# LogBoard.net
KiCad netlist of a schematic drawn in EAGLE
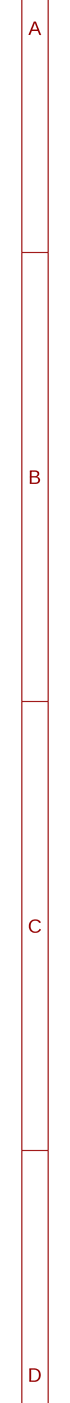
[diagram p0: schematic, sheet 1, part 1 of 2]
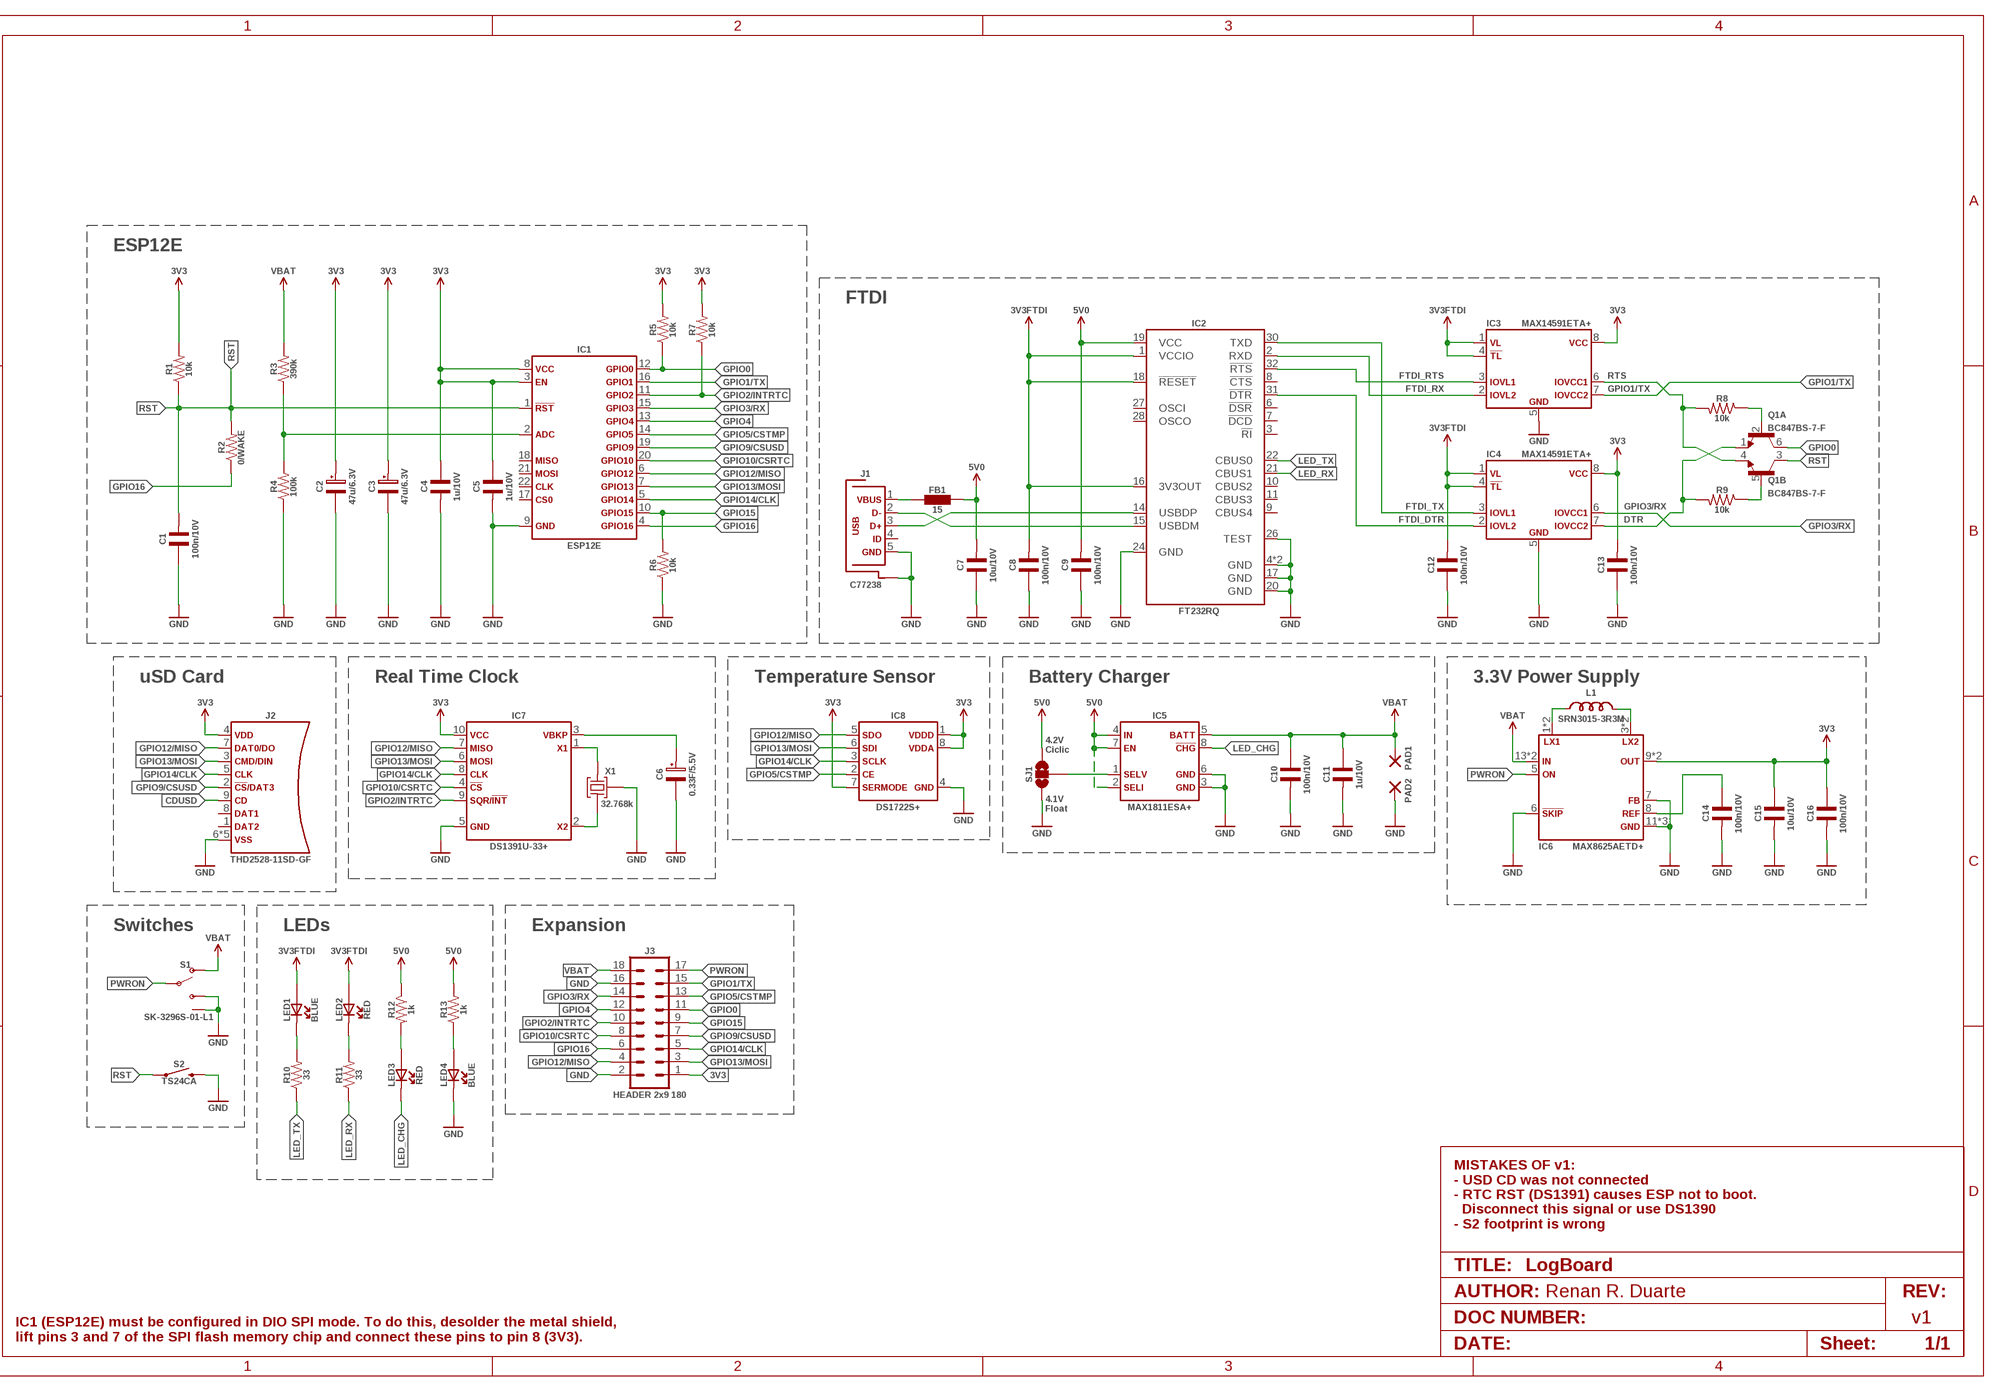
[diagram p1: schematic, sheet 1, part 2 of 2]

(export (version "E")
  (design (tool "Eeschema 10.0.6"))
  (components
    (comp (ref "C1")
      (value "100n/10V")
      (footprint "eagle-import:C-SMD-0603")
      (libsource (lib "eagle-import") (part "1-CAPACITORSMD-0603"))
    )
    (comp (ref "C2")
      (value "47u/6.3V")
      (footprint "eagle-import:C-SMD-CT3528")
      (libsource (lib "eagle-import") (part "1-CAPACITOR-POLCT3528"))
    )
    (comp (ref "C3")
      (value "47u/6.3V")
      (footprint "eagle-import:C-SMD-CT3528")
      (libsource (lib "eagle-import") (part "1-CAPACITOR-POLCT3528"))
    )
    (comp (ref "C4")
      (value "1u/10V")
      (footprint "eagle-import:C-SMD-0603")
      (libsource (lib "eagle-import") (part "1-CAPACITORSMD-0603"))
    )
    (comp (ref "C5")
      (value "1u/10V")
      (footprint "eagle-import:C-SMD-0603")
      (libsource (lib "eagle-import") (part "1-CAPACITORSMD-0603"))
    )
    (comp (ref "C6")
      (value "0.33F/5.5V")
      (footprint "eagle-import:C-PTH-5X11.5")
      (libsource (lib "eagle-import") (part "1-CAPACITOR-POL5X11.5"))
    )
    (comp (ref "C7")
      (value "10u/10V")
      (footprint "eagle-import:C-SMD-0603")
      (libsource (lib "eagle-import") (part "1-CAPACITORSMD-0603"))
    )
    (comp (ref "C8")
      (value "100n/10V")
      (footprint "eagle-import:C-SMD-0603")
      (libsource (lib "eagle-import") (part "1-CAPACITORSMD-0603"))
    )
    (comp (ref "C9")
      (value "100n/10V")
      (footprint "eagle-import:C-SMD-0603")
      (libsource (lib "eagle-import") (part "1-CAPACITORSMD-0603"))
    )
    (comp (ref "C10")
      (value "100n/10V")
      (footprint "eagle-import:C-SMD-0603")
      (libsource (lib "eagle-import") (part "1-CAPACITORSMD-0603"))
    )
    (comp (ref "C11")
      (value "1u/10V")
      (footprint "eagle-import:C-SMD-0603")
      (libsource (lib "eagle-import") (part "1-CAPACITORSMD-0603"))
    )
    (comp (ref "C12")
      (value "100n/10V")
      (footprint "eagle-import:C-SMD-0603")
      (libsource (lib "eagle-import") (part "1-CAPACITORSMD-0603"))
    )
    (comp (ref "C13")
      (value "100n/10V")
      (footprint "eagle-import:C-SMD-0603")
      (libsource (lib "eagle-import") (part "1-CAPACITORSMD-0603"))
    )
    (comp (ref "C14")
      (value "100n/10V")
      (footprint "eagle-import:C-SMD-0603")
      (libsource (lib "eagle-import") (part "1-CAPACITORSMD-0603"))
    )
    (comp (ref "C15")
      (value "10u/10V")
      (footprint "eagle-import:C-SMD-0603")
      (libsource (lib "eagle-import") (part "1-CAPACITORSMD-0603"))
    )
    (comp (ref "C16")
      (value "100n/10V")
      (footprint "eagle-import:C-SMD-0603")
      (libsource (lib "eagle-import") (part "1-CAPACITORSMD-0603"))
    )
    (comp (ref "FB1")
      (value "15")
      (footprint "eagle-import:R-SMD-0603")
      (libsource (lib "eagle-import") (part "FB-0603"))
    )
    (comp (ref "IC1")
      (value "ESP12E")
      (footprint "eagle-import:IC-ESP8266-12E")
      (libsource (lib "eagle-import") (part "IC-ESP8266-12E"))
    )
    (comp (ref "IC2")
      (value "FT232RQ")
      (footprint "eagle-import:IC-QFN32")
      (libsource (lib "eagle-import") (part "IC-FT232RQ"))
    )
    (comp (ref "IC3")
      (value "MAX14591ETA+")
      (footprint "eagle-import:IC-TDFN8")
      (libsource (lib "eagle-import") (part "IC-MAX14591"))
    )
    (comp (ref "IC4")
      (value "MAX14591ETA+")
      (footprint "eagle-import:IC-TDFN8")
      (libsource (lib "eagle-import") (part "IC-MAX14591"))
    )
    (comp (ref "IC5")
      (value "MAX1811ESA+")
      (footprint "eagle-import:IC-SO8")
      (libsource (lib "eagle-import") (part "IC-MAX1811"))
    )
    (comp (ref "IC6")
      (value "MAX8625AETD+")
      (footprint "eagle-import:IC-TDFN14")
      (libsource (lib "eagle-import") (part "IC-MAX8625"))
    )
    (comp (ref "IC7")
      (value "DS1391U-33+")
      (footprint "eagle-import:IC-USOP10")
      (libsource (lib "eagle-import") (part "IC-DS1394"))
    )
    (comp (ref "IC8")
      (value "DS1722S+")
      (footprint "eagle-import:IC-SO8")
      (libsource (lib "eagle-import") (part "IC-DS1722"))
    )
    (comp (ref "J1")
      (value "C77238")
      (footprint "eagle-import:CN-MICRO-USB")
      (libsource (lib "eagle-import") (part "CN-MICRO-USB"))
    )
    (comp (ref "J2")
      (value "THD2528-11SD-GF")
      (footprint "eagle-import:CN-MICROSD")
      (libsource (lib "eagle-import") (part "CN-MICROSD"))
    )
    (comp (ref "J3")
      (value "HEADER 2x9 180")
      (footprint "eagle-import:PH-9X2-180")
      (libsource (lib "eagle-import") (part "PIN-HEADER-9X2"))
    )
    (comp (ref "L1")
      (value "SRN3015-3R3M")
      (footprint "eagle-import:L-SMD-3X3")
      (libsource (lib "eagle-import") (part "2-INDUCTOR3X3"))
    )
    (comp (ref "LED1")
      (value "BLUE")
      (footprint "eagle-import:LED-SMD-0603")
      (libsource (lib "eagle-import") (part "LED0603"))
    )
    (comp (ref "LED2")
      (value "RED")
      (footprint "eagle-import:LED-SMD-0603")
      (libsource (lib "eagle-import") (part "LED0603"))
    )
    (comp (ref "LED3")
      (value "RED")
      (footprint "eagle-import:LED-SMD-0603")
      (libsource (lib "eagle-import") (part "LED0603"))
    )
    (comp (ref "LED4")
      (value "BLUE")
      (footprint "eagle-import:LED-SMD-0603")
      (libsource (lib "eagle-import") (part "LED0603"))
    )
    (comp (ref "PAD1")
      (value "SMD2")
      (footprint "eagle-import:SMD1,27-2,54")
      (libsource (lib "eagle-import") (part "SMD2"))
    )
    (comp (ref "PAD2")
      (value "SMD2")
      (footprint "eagle-import:SMD1,27-2,54")
      (libsource (lib "eagle-import") (part "SMD2"))
    )
    (comp (ref "Q1")
      (value "BC847BS-7-F")
      (footprint "eagle-import:IC-SOT363")
      (libsource (lib "eagle-import") (part "NPN-DUAL"))
    )
    (comp (ref "R1")
      (value "10k")
      (footprint "eagle-import:R-SMD-0603")
      (libsource (lib "eagle-import") (part "0-RESISTORSMD-0603"))
    )
    (comp (ref "R2")
      (value "0/WAKE")
      (footprint "eagle-import:R-SMD-0603")
      (libsource (lib "eagle-import") (part "0-RESISTORSMD-0603"))
    )
    (comp (ref "R3")
      (value "390k")
      (footprint "eagle-import:R-SMD-0603")
      (libsource (lib "eagle-import") (part "0-RESISTORSMD-0603"))
    )
    (comp (ref "R4")
      (value "100k")
      (footprint "eagle-import:R-SMD-0603")
      (libsource (lib "eagle-import") (part "0-RESISTORSMD-0603"))
    )
    (comp (ref "R5")
      (value "10k")
      (footprint "eagle-import:R-SMD-0603")
      (libsource (lib "eagle-import") (part "0-RESISTORSMD-0603"))
    )
    (comp (ref "R6")
      (value "10k")
      (footprint "eagle-import:R-SMD-0603")
      (libsource (lib "eagle-import") (part "0-RESISTORSMD-0603"))
    )
    (comp (ref "R7")
      (value "10k")
      (footprint "eagle-import:R-SMD-0603")
      (libsource (lib "eagle-import") (part "0-RESISTORSMD-0603"))
    )
    (comp (ref "R8")
      (value "10k")
      (footprint "eagle-import:R-SMD-0603")
      (libsource (lib "eagle-import") (part "0-RESISTORSMD-0603"))
    )
    (comp (ref "R9")
      (value "10k")
      (footprint "eagle-import:R-SMD-0603")
      (libsource (lib "eagle-import") (part "0-RESISTORSMD-0603"))
    )
    (comp (ref "R10")
      (value "33")
      (footprint "eagle-import:R-SMD-0603")
      (libsource (lib "eagle-import") (part "0-RESISTORSMD-0603"))
    )
    (comp (ref "R11")
      (value "33")
      (footprint "eagle-import:R-SMD-0603")
      (libsource (lib "eagle-import") (part "0-RESISTORSMD-0603"))
    )
    (comp (ref "R12")
      (value "1k")
      (footprint "eagle-import:R-SMD-0603")
      (libsource (lib "eagle-import") (part "0-RESISTORSMD-0603"))
    )
    (comp (ref "R13")
      (value "1k")
      (footprint "eagle-import:R-SMD-0603")
      (libsource (lib "eagle-import") (part "0-RESISTORSMD-0603"))
    )
    (comp (ref "S1")
      (value "SK-3296S-01-L1")
      (footprint "eagle-import:SWITCH_SPST_SMD_A")
      (libsource (lib "eagle-import") (part "SWITCH-SPDT-SMD-RIGHT-ANGLE"))
    )
    (comp (ref "S2")
      (value "TS24CA")
      (footprint "eagle-import:TACTILE_SWITCH_SMD_RIGHT_ANGLE")
      (libsource (lib "eagle-import") (part "MOMENTARY-SWITCH-SPST-SMD-RIGHT-ANGLE"))
    )
    (comp (ref "SJ1")
      (value "SJ-3")
      (footprint "eagle-import:SJ-3")
      (libsource (lib "eagle-import") (part "SJ-3"))
    )
    (comp (ref "X1")
      (value "32.768k")
      (footprint "eagle-import:CRYSTAL-SMD-7X1.5")
      (libsource (lib "eagle-import") (part "CRYSTAL"))
    )
  )
  (nets
    (net (code "1") (name "/DTR") (class "Default")
      (node (ref "IC4") (pin "7") (pinfunction "IOVCC2_7") (pintype "bidirectional"))
      (node (ref "Q1") (pin "1") (pinfunction "E_1") (pintype "passive"))
      (node (ref "R9") (pin "P$2") (pinfunction "2_P$2") (pintype "passive"))
    )
    (net (code "2") (name "/FTDI_DTR") (class "Default")
      (node (ref "IC2") (pin "31") (pinfunction "~{DTR}_31") (pintype "output"))
      (node (ref "IC4") (pin "2") (pinfunction "IOVL2_2") (pintype "bidirectional"))
    )
    (net (code "3") (name "/FTDI_RTS") (class "Default")
      (node (ref "IC2") (pin "32") (pinfunction "~{RTS}_32") (pintype "output"))
      (node (ref "IC3") (pin "3") (pinfunction "IOVL1_3") (pintype "bidirectional"))
    )
    (net (code "4") (name "/FTDI_RX") (class "Default")
      (node (ref "IC2") (pin "2") (pinfunction "RXD_2") (pintype "input"))
      (node (ref "IC3") (pin "2") (pinfunction "IOVL2_2") (pintype "bidirectional"))
    )
    (net (code "5") (name "/FTDI_TX") (class "Default")
      (node (ref "IC2") (pin "30") (pinfunction "TXD_30") (pintype "output"))
      (node (ref "IC4") (pin "3") (pinfunction "IOVL1_3") (pintype "bidirectional"))
    )
    (net (code "6") (name "/RTS") (class "Default")
      (node (ref "IC3") (pin "6") (pinfunction "IOVCC1_6") (pintype "bidirectional"))
      (node (ref "Q1") (pin "4") (pinfunction "E_4") (pintype "passive"))
      (node (ref "R8") (pin "P$2") (pinfunction "2_P$2") (pintype "passive"))
    )
    (net (code "7") (name "3V3") (class "Default")
      (node (ref "C13") (pin "P$2") (pinfunction "2_P$2") (pintype "passive"))
      (node (ref "C15") (pin "P$1") (pinfunction "1_P$1") (pintype "passive"))
      (node (ref "C16") (pin "P$1") (pinfunction "1_P$1") (pintype "passive"))
      (node (ref "C2") (pin "+") (pinfunction "P_+") (pintype "passive"))
      (node (ref "C3") (pin "+") (pinfunction "P_+") (pintype "passive"))
      (node (ref "C4") (pin "P$1") (pinfunction "1_P$1") (pintype "passive"))
      (node (ref "C5") (pin "P$1") (pinfunction "1_P$1") (pintype "passive"))
      (node (ref "IC1") (pin "3") (pinfunction "EN_3") (pintype "bidirectional"))
      (node (ref "IC1") (pin "8") (pinfunction "VCC_8") (pintype "bidirectional"))
      (node (ref "IC3") (pin "8") (pinfunction "VCC_8") (pintype "bidirectional"))
      (node (ref "IC4") (pin "8") (pinfunction "VCC_8") (pintype "bidirectional"))
      (node (ref "IC6") (pin "10") (pinfunction "OUT_10") (pintype "bidirectional"))
      (node (ref "IC6") (pin "9") (pinfunction "OUT_9") (pintype "bidirectional"))
      (node (ref "IC7") (pin "10") (pinfunction "VCC_10") (pintype "bidirectional"))
      (node (ref "IC8") (pin "1") (pinfunction "VDDD_1") (pintype "bidirectional"))
      (node (ref "IC8") (pin "7") (pinfunction "SERMODE_7") (pintype "bidirectional"))
      (node (ref "IC8") (pin "8") (pinfunction "VDDA_8") (pintype "bidirectional"))
      (node (ref "J2") (pin "4") (pinfunction "VDD_4") (pintype "bidirectional"))
      (node (ref "J3") (pin "1") (pinfunction "1_1") (pintype "passive"))
      (node (ref "R1") (pin "P$2") (pinfunction "2_P$2") (pintype "passive"))
      (node (ref "R5") (pin "P$2") (pinfunction "2_P$2") (pintype "passive"))
      (node (ref "R7") (pin "P$2") (pinfunction "2_P$2") (pintype "passive"))
    )
    (net (code "8") (name "3V3FTDI") (class "Default")
      (node (ref "C12") (pin "P$2") (pinfunction "2_P$2") (pintype "passive"))
      (node (ref "C8") (pin "P$2") (pinfunction "2_P$2") (pintype "passive"))
      (node (ref "IC2") (pin "1") (pinfunction "VCCIO_1") (pintype "power_in"))
      (node (ref "IC2") (pin "16") (pinfunction "3V3OUT_16") (pintype "output"))
      (node (ref "IC2") (pin "18") (pinfunction "~{RESET}_18") (pintype "input"))
      (node (ref "IC3") (pin "1") (pinfunction "VL_1") (pintype "bidirectional"))
      (node (ref "IC3") (pin "4") (pinfunction "~{TL}_4") (pintype "bidirectional"))
      (node (ref "IC4") (pin "1") (pinfunction "VL_1") (pintype "bidirectional"))
      (node (ref "IC4") (pin "4") (pinfunction "~{TL}_4") (pintype "bidirectional"))
      (node (ref "LED1") (pin "A") (pinfunction "A_A") (pintype "passive"))
      (node (ref "LED2") (pin "A") (pinfunction "A_A") (pintype "passive"))
    )
    (net (code "9") (name "5V0") (class "Default")
      (node (ref "C7") (pin "P$2") (pinfunction "2_P$2") (pintype "passive"))
      (node (ref "C9") (pin "P$2") (pinfunction "2_P$2") (pintype "passive"))
      (node (ref "FB1") (pin "P$2") (pinfunction "2_P$2") (pintype "passive"))
      (node (ref "IC2") (pin "19") (pinfunction "VCC_19") (pintype "power_in"))
      (node (ref "IC5") (pin "2") (pinfunction "SELI_2") (pintype "bidirectional"))
      (node (ref "IC5") (pin "4") (pinfunction "IN_4") (pintype "bidirectional"))
      (node (ref "IC5") (pin "7") (pinfunction "EN_7") (pintype "bidirectional"))
      (node (ref "R12") (pin "P$1") (pinfunction "1_P$1") (pintype "passive"))
      (node (ref "R13") (pin "P$2") (pinfunction "2_P$2") (pintype "passive"))
      (node (ref "SJ1") (pin "1") (pinfunction "1_1") (pintype "passive"))
    )
    (net (code "10") (name "CDUSD") (class "Default")
      (node (ref "J2") (pin "9") (pinfunction "CD_9") (pintype "bidirectional"))
    )
    (net (code "11") (name "GND") (class "Default")
      (node (ref "C1") (pin "P$1") (pinfunction "1_P$1") (pintype "passive"))
      (node (ref "C10") (pin "P$2") (pinfunction "2_P$2") (pintype "passive"))
      (node (ref "C11") (pin "P$2") (pinfunction "2_P$2") (pintype "passive"))
      (node (ref "C12") (pin "P$1") (pinfunction "1_P$1") (pintype "passive"))
      (node (ref "C13") (pin "P$1") (pinfunction "1_P$1") (pintype "passive"))
      (node (ref "C14") (pin "P$2") (pinfunction "2_P$2") (pintype "passive"))
      (node (ref "C15") (pin "P$2") (pinfunction "2_P$2") (pintype "passive"))
      (node (ref "C16") (pin "P$2") (pinfunction "2_P$2") (pintype "passive"))
      (node (ref "C2") (pin "-") (pinfunction "N_-") (pintype "passive"))
      (node (ref "C3") (pin "-") (pinfunction "N_-") (pintype "passive"))
      (node (ref "C4") (pin "P$2") (pinfunction "2_P$2") (pintype "passive"))
      (node (ref "C5") (pin "P$2") (pinfunction "2_P$2") (pintype "passive"))
      (node (ref "C6") (pin "N") (pinfunction "N_N") (pintype "passive"))
      (node (ref "C7") (pin "P$1") (pinfunction "1_P$1") (pintype "passive"))
      (node (ref "C8") (pin "P$1") (pinfunction "1_P$1") (pintype "passive"))
      (node (ref "C9") (pin "P$1") (pinfunction "1_P$1") (pintype "passive"))
      (node (ref "IC1") (pin "9") (pinfunction "GND_9") (pintype "bidirectional"))
      (node (ref "IC2") (pin "17") (pinfunction "GND_17") (pintype "power_in"))
      (node (ref "IC2") (pin "20") (pinfunction "GND_20") (pintype "power_in"))
      (node (ref "IC2") (pin "24") (pinfunction "GND_24") (pintype "power_in"))
      (node (ref "IC2") (pin "26") (pinfunction "TEST_26") (pintype "input"))
      (node (ref "IC2") (pin "4") (pinfunction "GND_4") (pintype "power_in"))
      (node (ref "IC2") (pin "GND") (pinfunction "GND_GND") (pintype "power_in"))
      (node (ref "IC3") (pin "5") (pinfunction "GND_5") (pintype "bidirectional"))
      (node (ref "IC4") (pin "5") (pinfunction "GND_5") (pintype "bidirectional"))
      (node (ref "IC5") (pin "3") (pinfunction "GND_3") (pintype "bidirectional"))
      (node (ref "IC5") (pin "6") (pinfunction "GND_6") (pintype "bidirectional"))
      (node (ref "IC6") (pin "11") (pinfunction "GND_11") (pintype "bidirectional"))
      (node (ref "IC6") (pin "12") (pinfunction "GND_12") (pintype "bidirectional"))
      (node (ref "IC6") (pin "6") (pinfunction "~{SKIP}_6") (pintype "bidirectional"))
      (node (ref "IC6") (pin "7") (pinfunction "FB_7") (pintype "bidirectional"))
      (node (ref "IC6") (pin "TP") (pinfunction "GND_TP") (pintype "bidirectional"))
      (node (ref "IC7") (pin "5") (pinfunction "GND_5") (pintype "bidirectional"))
      (node (ref "IC8") (pin "4") (pinfunction "GND_4") (pintype "bidirectional"))
      (node (ref "J1") (pin "5") (pinfunction "GND_5") (pintype "passive"))
      (node (ref "J1") (pin "SHELL") (pinfunction "SHIELD_SHELL") (pintype "passive"))
      (node (ref "J1") (pin "SHELL1") (pinfunction "SHIELD_SHELL1") (pintype "passive"))
      (node (ref "J1") (pin "SHELL2") (pinfunction "SHIELD_SHELL2") (pintype "passive"))
      (node (ref "J1") (pin "SHELL3") (pinfunction "SHIELD_SHELL3") (pintype "passive"))
      (node (ref "J2") (pin "6") (pinfunction "VSS_6") (pintype "bidirectional"))
      (node (ref "J2") (pin "G1") (pinfunction "VSS_G1") (pintype "bidirectional"))
      (node (ref "J2") (pin "G2") (pinfunction "VSS_G2") (pintype "bidirectional"))
      (node (ref "J2") (pin "G3") (pinfunction "VSS_G3") (pintype "bidirectional"))
      (node (ref "J2") (pin "G4") (pinfunction "VSS_G4") (pintype "bidirectional"))
      (node (ref "J3") (pin "16") (pinfunction "16_16") (pintype "passive"))
      (node (ref "J3") (pin "2") (pinfunction "2_2") (pintype "passive"))
      (node (ref "LED4") (pin "C") (pinfunction "C_C") (pintype "passive"))
      (node (ref "PAD2") (pin "1") (pinfunction "P_1") (pintype "passive"))
      (node (ref "R4") (pin "P$1") (pinfunction "1_P$1") (pintype "passive"))
      (node (ref "R6") (pin "P$1") (pinfunction "1_P$1") (pintype "passive"))
      (node (ref "S1") (pin "3") (pinfunction "S_3") (pintype "passive"))
      (node (ref "S1") (pin "GND1") (pinfunction "P$1_GND1") (pintype "bidirectional"))
      (node (ref "S1") (pin "GND2") (pinfunction "P$1_GND2") (pintype "bidirectional"))
      (node (ref "S1") (pin "GND3") (pinfunction "P$1_GND3") (pintype "bidirectional"))
      (node (ref "S1") (pin "GND4") (pinfunction "P$1_GND4") (pintype "bidirectional"))
      (node (ref "S2") (pin "2") (pinfunction "2_2") (pintype "passive"))
      (node (ref "SJ1") (pin "3") (pinfunction "3_3") (pintype "passive"))
      (node (ref "X1") (pin "3") (pinfunction "2_3") (pintype "passive"))
      (node (ref "X1") (pin "4") (pinfunction "2_4") (pintype "passive"))
    )
    (net (code "12") (name "GPIO0") (class "Default")
      (node (ref "IC1") (pin "12") (pinfunction "GPIO0_12") (pintype "bidirectional"))
      (node (ref "J3") (pin "11") (pinfunction "11_11") (pintype "passive"))
      (node (ref "Q1") (pin "6") (pinfunction "C_6") (pintype "passive"))
      (node (ref "R5") (pin "P$1") (pinfunction "1_P$1") (pintype "passive"))
    )
    (net (code "13") (name "GPIO1{slash}TX") (class "Default")
      (node (ref "IC1") (pin "16") (pinfunction "GPIO1_16") (pintype "bidirectional"))
      (node (ref "IC3") (pin "7") (pinfunction "IOVCC2_7") (pintype "bidirectional"))
      (node (ref "J3") (pin "15") (pinfunction "15_15") (pintype "passive"))
    )
    (net (code "14") (name "GPIO2{slash}INTRTC") (class "Default")
      (node (ref "IC1") (pin "11") (pinfunction "GPIO2_11") (pintype "bidirectional"))
      (node (ref "IC7") (pin "9") (pinfunction "INT_9") (pintype "bidirectional"))
      (node (ref "J3") (pin "10") (pinfunction "10_10") (pintype "passive"))
      (node (ref "R7") (pin "P$1") (pinfunction "1_P$1") (pintype "passive"))
    )
    (net (code "15") (name "GPIO3{slash}RX") (class "Default")
      (node (ref "IC1") (pin "15") (pinfunction "GPIO3_15") (pintype "bidirectional"))
      (node (ref "IC4") (pin "6") (pinfunction "IOVCC1_6") (pintype "bidirectional"))
      (node (ref "J3") (pin "14") (pinfunction "14_14") (pintype "passive"))
    )
    (net (code "16") (name "GPIO4") (class "Default")
      (node (ref "IC1") (pin "13") (pinfunction "GPIO4_13") (pintype "bidirectional"))
      (node (ref "J3") (pin "12") (pinfunction "12_12") (pintype "passive"))
    )
    (net (code "17") (name "GPIO5{slash}CSTMP") (class "Default")
      (node (ref "IC1") (pin "14") (pinfunction "GPIO5_14") (pintype "bidirectional"))
      (node (ref "IC8") (pin "2") (pinfunction "CE_2") (pintype "bidirectional"))
      (node (ref "J3") (pin "13") (pinfunction "13_13") (pintype "passive"))
    )
    (net (code "18") (name "GPIO9{slash}CSUSD") (class "Default")
      (node (ref "IC1") (pin "19") (pinfunction "GPIO9_19") (pintype "bidirectional"))
      (node (ref "J2") (pin "2") (pinfunction "CD_DAT3_CS_2") (pintype "bidirectional"))
      (node (ref "J3") (pin "7") (pinfunction "7_7") (pintype "passive"))
    )
    (net (code "19") (name "GPIO10{slash}CSRTC") (class "Default")
      (node (ref "IC1") (pin "20") (pinfunction "GPIO10_20") (pintype "bidirectional"))
      (node (ref "IC7") (pin "4") (pinfunction "CS_4") (pintype "bidirectional"))
      (node (ref "J3") (pin "8") (pinfunction "8_8") (pintype "passive"))
    )
    (net (code "20") (name "GPIO12{slash}MISO") (class "Default")
      (node (ref "IC1") (pin "6") (pinfunction "GPIO12_6") (pintype "bidirectional"))
      (node (ref "IC7") (pin "7") (pinfunction "MISO_7") (pintype "bidirectional"))
      (node (ref "IC8") (pin "5") (pinfunction "SDO_5") (pintype "bidirectional"))
      (node (ref "J2") (pin "7") (pinfunction "DAT0_DO_7") (pintype "bidirectional"))
      (node (ref "J3") (pin "4") (pinfunction "4_4") (pintype "passive"))
    )
    (net (code "21") (name "GPIO13{slash}MOSI") (class "Default")
      (node (ref "IC1") (pin "7") (pinfunction "GPIO13_7") (pintype "bidirectional"))
      (node (ref "IC7") (pin "6") (pinfunction "MOSI_6") (pintype "bidirectional"))
      (node (ref "IC8") (pin "6") (pinfunction "SDI_6") (pintype "bidirectional"))
      (node (ref "J2") (pin "3") (pinfunction "CMD_DIN_3") (pintype "bidirectional"))
      (node (ref "J3") (pin "3") (pinfunction "3_3") (pintype "passive"))
    )
    (net (code "22") (name "GPIO14{slash}CLK") (class "Default")
      (node (ref "IC1") (pin "5") (pinfunction "GPIO14_5") (pintype "bidirectional"))
      (node (ref "IC7") (pin "8") (pinfunction "CLK_8") (pintype "bidirectional"))
      (node (ref "IC8") (pin "3") (pinfunction "SCLK_3") (pintype "bidirectional"))
      (node (ref "J2") (pin "5") (pinfunction "CLK_5") (pintype "bidirectional"))
      (node (ref "J3") (pin "5") (pinfunction "5_5") (pintype "passive"))
    )
    (net (code "23") (name "GPIO15") (class "Default")
      (node (ref "IC1") (pin "10") (pinfunction "GPIO15_10") (pintype "bidirectional"))
      (node (ref "J3") (pin "9") (pinfunction "9_9") (pintype "passive"))
      (node (ref "R6") (pin "P$2") (pinfunction "2_P$2") (pintype "passive"))
    )
    (net (code "24") (name "GPIO16") (class "Default")
      (node (ref "IC1") (pin "4") (pinfunction "GPIO16_4") (pintype "bidirectional"))
      (node (ref "J3") (pin "6") (pinfunction "6_6") (pintype "passive"))
      (node (ref "R2") (pin "P$1") (pinfunction "1_P$1") (pintype "passive"))
    )
    (net (code "25") (name "LED_CHG") (class "Default")
      (node (ref "IC5") (pin "8") (pinfunction "~{CHG}_8") (pintype "bidirectional"))
      (node (ref "LED3") (pin "C") (pinfunction "C_C") (pintype "passive"))
    )
    (net (code "26") (name "LED_RX") (class "Default")
      (node (ref "IC2") (pin "21") (pinfunction "CBUS1_21") (pintype "bidirectional"))
      (node (ref "R11") (pin "P$1") (pinfunction "1_P$1") (pintype "passive"))
    )
    (net (code "27") (name "LED_TX") (class "Default")
      (node (ref "IC2") (pin "22") (pinfunction "CBUS0_22") (pintype "bidirectional"))
      (node (ref "R10") (pin "P$1") (pinfunction "1_P$1") (pintype "passive"))
    )
    (net (code "28") (name "Net-(C14-1)") (class "Default")
      (node (ref "C14") (pin "P$1") (pinfunction "1_P$1") (pintype "passive"))
      (node (ref "IC6") (pin "8") (pinfunction "REF_8") (pintype "bidirectional"))
    )
    (net (code "29") (name "Net-(FB1-1)") (class "Default")
      (node (ref "FB1") (pin "P$1") (pinfunction "1_P$1") (pintype "passive"))
      (node (ref "J1") (pin "1") (pinfunction "VBUS_1") (pintype "passive"))
    )
    (net (code "30") (name "Net-(IC1-ADC)") (class "Default")
      (node (ref "IC1") (pin "2") (pinfunction "ADC_2") (pintype "bidirectional"))
      (node (ref "R3") (pin "P$1") (pinfunction "1_P$1") (pintype "passive"))
      (node (ref "R4") (pin "P$2") (pinfunction "2_P$2") (pintype "passive"))
    )
    (net (code "31") (name "Net-(IC2-USBDM)") (class "Default")
      (node (ref "IC2") (pin "15") (pinfunction "USBDM_15") (pintype "bidirectional"))
      (node (ref "J1") (pin "2") (pinfunction "D-_2") (pintype "passive"))
    )
    (net (code "32") (name "Net-(IC2-USBDP)") (class "Default")
      (node (ref "IC2") (pin "14") (pinfunction "USBDP_14") (pintype "bidirectional"))
      (node (ref "J1") (pin "3") (pinfunction "D+_3") (pintype "passive"))
    )
    (net (code "33") (name "Net-(IC5-SELV)") (class "Default")
      (node (ref "IC5") (pin "1") (pinfunction "SELV_1") (pintype "bidirectional"))
      (node (ref "SJ1") (pin "2") (pinfunction "2_2") (pintype "passive"))
    )
    (net (code "34") (name "Net-(IC7-VBKP)") (class "Default")
      (node (ref "C6") (pin "P") (pinfunction "P_P") (pintype "passive"))
      (node (ref "IC7") (pin "3") (pinfunction "VBKP_3") (pintype "bidirectional"))
    )
    (net (code "35") (name "Net-(IC7-X1)") (class "Default")
      (node (ref "IC7") (pin "1") (pinfunction "X1_1") (pintype "bidirectional"))
      (node (ref "X1") (pin "2") (pinfunction "3_2") (pintype "passive"))
    )
    (net (code "36") (name "Net-(IC7-X2)") (class "Default")
      (node (ref "IC7") (pin "2") (pinfunction "X2_2") (pintype "bidirectional"))
      (node (ref "X1") (pin "1") (pinfunction "1_1") (pintype "passive"))
    )
    (net (code "37") (name "Net-(L1-1)") (class "Default")
      (node (ref "IC6") (pin "1") (pinfunction "LX1_1") (pintype "bidirectional"))
      (node (ref "IC6") (pin "2") (pinfunction "LX1_2") (pintype "bidirectional"))
      (node (ref "L1") (pin "P$1") (pinfunction "1_P$1") (pintype "passive"))
    )
    (net (code "38") (name "Net-(L1-2)") (class "Default")
      (node (ref "IC6") (pin "3") (pinfunction "LX2_3") (pintype "bidirectional"))
      (node (ref "IC6") (pin "4") (pinfunction "LX2_4") (pintype "bidirectional"))
      (node (ref "L1") (pin "P$2") (pinfunction "2_P$2") (pintype "passive"))
    )
    (net (code "39") (name "Net-(Q1A-B)") (class "Default")
      (node (ref "Q1") (pin "2") (pinfunction "B_2") (pintype "passive"))
      (node (ref "R8") (pin "P$1") (pinfunction "1_P$1") (pintype "passive"))
    )
    (net (code "40") (name "Net-(Q1B-B)") (class "Default")
      (node (ref "Q1") (pin "5") (pinfunction "B_5") (pintype "passive"))
      (node (ref "R9") (pin "P$1") (pinfunction "1_P$1") (pintype "passive"))
    )
    (net (code "41") (name "Net-(R10-2)") (class "Default")
      (node (ref "LED1") (pin "C") (pinfunction "C_C") (pintype "passive"))
      (node (ref "R10") (pin "P$2") (pinfunction "2_P$2") (pintype "passive"))
    )
    (net (code "42") (name "Net-(R11-2)") (class "Default")
      (node (ref "LED2") (pin "C") (pinfunction "C_C") (pintype "passive"))
      (node (ref "R11") (pin "P$2") (pinfunction "2_P$2") (pintype "passive"))
    )
    (net (code "43") (name "Net-(R12-2)") (class "Default")
      (node (ref "LED3") (pin "A") (pinfunction "A_A") (pintype "passive"))
      (node (ref "R12") (pin "P$2") (pinfunction "2_P$2") (pintype "passive"))
    )
    (net (code "44") (name "Net-(R13-1)") (class "Default")
      (node (ref "LED4") (pin "A") (pinfunction "A_A") (pintype "passive"))
      (node (ref "R13") (pin "P$1") (pinfunction "1_P$1") (pintype "passive"))
    )
    (net (code "45") (name "PWRON") (class "Default")
      (node (ref "IC6") (pin "5") (pinfunction "ON_5") (pintype "bidirectional"))
      (node (ref "J3") (pin "17") (pinfunction "17_17") (pintype "passive"))
      (node (ref "S1") (pin "2") (pinfunction "P_2") (pintype "passive"))
    )
    (net (code "46") (name "RST") (class "Default")
      (node (ref "C1") (pin "P$2") (pinfunction "2_P$2") (pintype "passive"))
      (node (ref "IC1") (pin "1") (pinfunction "RST_1") (pintype "bidirectional"))
      (node (ref "Q1") (pin "3") (pinfunction "C_3") (pintype "passive"))
      (node (ref "R1") (pin "P$1") (pinfunction "1_P$1") (pintype "passive"))
      (node (ref "R2") (pin "P$2") (pinfunction "2_P$2") (pintype "passive"))
      (node (ref "S2") (pin "1") (pinfunction "1_1") (pintype "passive"))
    )
    (net (code "47") (name "VBAT") (class "Default")
      (node (ref "C10") (pin "P$1") (pinfunction "1_P$1") (pintype "passive"))
      (node (ref "C11") (pin "P$1") (pinfunction "1_P$1") (pintype "passive"))
      (node (ref "IC5") (pin "5") (pinfunction "BATT_5") (pintype "bidirectional"))
      (node (ref "IC6") (pin "13") (pinfunction "IN_13") (pintype "bidirectional"))
      (node (ref "IC6") (pin "14") (pinfunction "IN_14") (pintype "bidirectional"))
      (node (ref "J3") (pin "18") (pinfunction "18_18") (pintype "passive"))
      (node (ref "PAD1") (pin "1") (pinfunction "P_1") (pintype "passive"))
      (node (ref "R3") (pin "P$2") (pinfunction "2_P$2") (pintype "passive"))
      (node (ref "S1") (pin "1") (pinfunction "O_1") (pintype "passive"))
    )
    (net (code "48") (name "unconnected-(IC1-CS0-Pad17)") (class "Default")
      (node (ref "IC1") (pin "17") (pinfunction "CS0_17") (pintype "bidirectional"))
    )
    (net (code "49") (name "unconnected-(IC1-MISO-Pad18)") (class "Default")
      (node (ref "IC1") (pin "18") (pinfunction "MISO_18") (pintype "bidirectional"))
    )
    (net (code "50") (name "unconnected-(IC1-MOSI-Pad21)") (class "Default")
      (node (ref "IC1") (pin "21") (pinfunction "MOSI_21") (pintype "bidirectional"))
    )
    (net (code "51") (name "unconnected-(IC1-SCLK-Pad22)") (class "Default")
      (node (ref "IC1") (pin "22") (pinfunction "SCLK_22") (pintype "bidirectional"))
    )
    (net (code "52") (name "unconnected-(IC2-CBUS2-Pad10)") (class "Default")
      (node (ref "IC2") (pin "10") (pinfunction "CBUS2_10") (pintype "bidirectional"))
    )
    (net (code "53") (name "unconnected-(IC2-CBUS3-Pad11)") (class "Default")
      (node (ref "IC2") (pin "11") (pinfunction "CBUS3_11") (pintype "bidirectional"))
    )
    (net (code "54") (name "unconnected-(IC2-CBUS4-Pad9)") (class "Default")
      (node (ref "IC2") (pin "9") (pinfunction "CBUS4_9") (pintype "bidirectional"))
    )
    (net (code "55") (name "unconnected-(IC2-OSCI-Pad27)") (class "Default")
      (node (ref "IC2") (pin "27") (pinfunction "OSCI_27") (pintype "input"))
    )
    (net (code "56") (name "unconnected-(IC2-OSCO-Pad28)") (class "Default")
      (node (ref "IC2") (pin "28") (pinfunction "OSCO_28") (pintype "output"))
    )
    (net (code "57") (name "unconnected-(IC2-~{CTS}-Pad8)") (class "Default")
      (node (ref "IC2") (pin "8") (pinfunction "~{CTS}_8") (pintype "input"))
    )
    (net (code "58") (name "unconnected-(IC2-~{DCD}-Pad7)") (class "Default")
      (node (ref "IC2") (pin "7") (pinfunction "~{DCD}_7") (pintype "input"))
    )
    (net (code "59") (name "unconnected-(IC2-~{DSR}-Pad6)") (class "Default")
      (node (ref "IC2") (pin "6") (pinfunction "~{DSR}_6") (pintype "input"))
    )
    (net (code "60") (name "unconnected-(IC2-~{RI}-Pad3)") (class "Default")
      (node (ref "IC2") (pin "3") (pinfunction "~{RI}_3") (pintype "input"))
    )
    (net (code "61") (name "unconnected-(J1-ID-Pad4)") (class "Default")
      (node (ref "J1") (pin "4") (pinfunction "ID_4") (pintype "passive"))
    )
    (net (code "62") (name "unconnected-(J2-DAT1-Pad8)") (class "Default")
      (node (ref "J2") (pin "8") (pinfunction "DAT1_8") (pintype "bidirectional"))
    )
    (net (code "63") (name "unconnected-(J2-DAT2-Pad1)") (class "Default")
      (node (ref "J2") (pin "1") (pinfunction "DAT2_1") (pintype "bidirectional"))
    )
  )
)
